# Main.net
KiCad netlist of a schematic drawn in Altium Designer
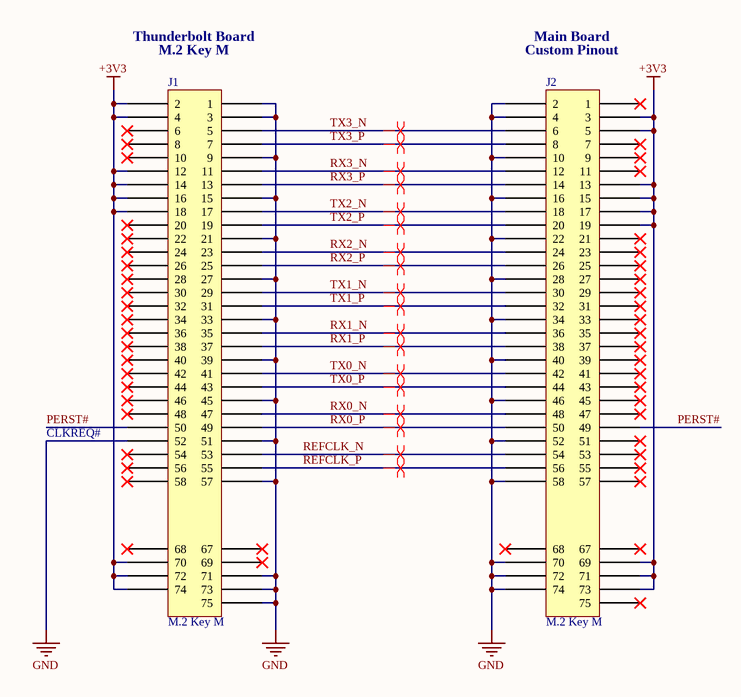
[diagram p0: Main.SchDoc]

(export (version "E")
  (design (tool "Eeschema 10.0.6"))
  (components
    (comp (ref "J1")
      (value "M.2 Key M")
      (footprint "PCB EDGE M.2 Key M")
      (libsource (lib "DSO") (part "M.2 Key M"))
    )
    (comp (ref "J2")
      (value "M.2 Key M")
      (footprint "PCB EDGE M.2 Key M")
      (libsource (lib "DSO") (part "M.2 Key M"))
    )
  )
  (nets
    (net (code "1") (name "+3V3") (class "Default")
      (node (ref "J1") (pin "12") (pinfunction "12_12") (pintype "passive"))
      (node (ref "J1") (pin "14") (pinfunction "14_14") (pintype "passive"))
      (node (ref "J1") (pin "16") (pinfunction "16_16") (pintype "passive"))
      (node (ref "J1") (pin "18") (pinfunction "18_18") (pintype "passive"))
      (node (ref "J1") (pin "2") (pinfunction "2_2") (pintype "passive"))
      (node (ref "J1") (pin "4") (pinfunction "4_4") (pintype "passive"))
      (node (ref "J1") (pin "70") (pinfunction "70_70") (pintype "passive"))
      (node (ref "J1") (pin "72") (pinfunction "72_72") (pintype "passive"))
      (node (ref "J1") (pin "74") (pinfunction "74_74") (pintype "passive"))
      (node (ref "J2") (pin "13") (pinfunction "13_13") (pintype "passive"))
      (node (ref "J2") (pin "15") (pinfunction "15_15") (pintype "passive"))
      (node (ref "J2") (pin "17") (pinfunction "17_17") (pintype "passive"))
      (node (ref "J2") (pin "19") (pinfunction "19_19") (pintype "passive"))
      (node (ref "J2") (pin "3") (pinfunction "3_3") (pintype "passive"))
      (node (ref "J2") (pin "5") (pinfunction "5_5") (pintype "passive"))
      (node (ref "J2") (pin "69") (pinfunction "69_69") (pintype "passive"))
      (node (ref "J2") (pin "71") (pinfunction "71_71") (pintype "passive"))
      (node (ref "J2") (pin "73") (pinfunction "73_73") (pintype "passive"))
    )
    (net (code "2") (name "/PERST#") (class "Default")
      (node (ref "J1") (pin "50") (pinfunction "50_50") (pintype "passive"))
      (node (ref "J2") (pin "49") (pinfunction "49_49") (pintype "passive"))
    )
    (net (code "3") (name "/REFCLK_N") (class "Default")
      (node (ref "J1") (pin "53") (pinfunction "53_53") (pintype "passive"))
      (node (ref "J2") (pin "54") (pinfunction "54_54") (pintype "passive"))
    )
    (net (code "4") (name "/REFCLK_P") (class "Default")
      (node (ref "J1") (pin "55") (pinfunction "55_55") (pintype "passive"))
      (node (ref "J2") (pin "56") (pinfunction "56_56") (pintype "passive"))
    )
    (net (code "5") (name "/RX0_N") (class "Default")
      (node (ref "J1") (pin "47") (pinfunction "47_47") (pintype "passive"))
      (node (ref "J2") (pin "48") (pinfunction "48_48") (pintype "passive"))
    )
    (net (code "6") (name "/RX0_P") (class "Default")
      (node (ref "J1") (pin "49") (pinfunction "49_49") (pintype "passive"))
      (node (ref "J2") (pin "50") (pinfunction "50_50") (pintype "passive"))
    )
    (net (code "7") (name "/RX1_N") (class "Default")
      (node (ref "J1") (pin "35") (pinfunction "35_35") (pintype "passive"))
      (node (ref "J2") (pin "36") (pinfunction "36_36") (pintype "passive"))
    )
    (net (code "8") (name "/RX1_P") (class "Default")
      (node (ref "J1") (pin "37") (pinfunction "37_37") (pintype "passive"))
      (node (ref "J2") (pin "38") (pinfunction "38_38") (pintype "passive"))
    )
    (net (code "9") (name "/RX2_N") (class "Default")
      (node (ref "J1") (pin "23") (pinfunction "23_23") (pintype "passive"))
      (node (ref "J2") (pin "24") (pinfunction "24_24") (pintype "passive"))
    )
    (net (code "10") (name "/RX2_P") (class "Default")
      (node (ref "J1") (pin "25") (pinfunction "25_25") (pintype "passive"))
      (node (ref "J2") (pin "26") (pinfunction "26_26") (pintype "passive"))
    )
    (net (code "11") (name "/RX3_N") (class "Default")
      (node (ref "J1") (pin "11") (pinfunction "11_11") (pintype "passive"))
      (node (ref "J2") (pin "12") (pinfunction "12_12") (pintype "passive"))
    )
    (net (code "12") (name "/RX3_P") (class "Default")
      (node (ref "J1") (pin "13") (pinfunction "13_13") (pintype "passive"))
      (node (ref "J2") (pin "14") (pinfunction "14_14") (pintype "passive"))
    )
    (net (code "13") (name "/TX0_N") (class "Default")
      (node (ref "J1") (pin "41") (pinfunction "41_41") (pintype "passive"))
      (node (ref "J2") (pin "42") (pinfunction "42_42") (pintype "passive"))
    )
    (net (code "14") (name "/TX0_P") (class "Default")
      (node (ref "J1") (pin "43") (pinfunction "43_43") (pintype "passive"))
      (node (ref "J2") (pin "44") (pinfunction "44_44") (pintype "passive"))
    )
    (net (code "15") (name "/TX1_N") (class "Default")
      (node (ref "J1") (pin "29") (pinfunction "29_29") (pintype "passive"))
      (node (ref "J2") (pin "30") (pinfunction "30_30") (pintype "passive"))
    )
    (net (code "16") (name "/TX1_P") (class "Default")
      (node (ref "J1") (pin "31") (pinfunction "31_31") (pintype "passive"))
      (node (ref "J2") (pin "32") (pinfunction "32_32") (pintype "passive"))
    )
    (net (code "17") (name "/TX2_N") (class "Default")
      (node (ref "J1") (pin "17") (pinfunction "17_17") (pintype "passive"))
      (node (ref "J2") (pin "18") (pinfunction "18_18") (pintype "passive"))
    )
    (net (code "18") (name "/TX2_P") (class "Default")
      (node (ref "J1") (pin "19") (pinfunction "19_19") (pintype "passive"))
      (node (ref "J2") (pin "20") (pinfunction "20_20") (pintype "passive"))
    )
    (net (code "19") (name "/TX3_N") (class "Default")
      (node (ref "J1") (pin "5") (pinfunction "5_5") (pintype "passive"))
      (node (ref "J2") (pin "6") (pinfunction "6_6") (pintype "passive"))
    )
    (net (code "20") (name "/TX3_P") (class "Default")
      (node (ref "J1") (pin "7") (pinfunction "7_7") (pintype "passive"))
      (node (ref "J2") (pin "8") (pinfunction "8_8") (pintype "passive"))
    )
    (net (code "21") (name "GND") (class "Default")
      (node (ref "J1") (pin "1") (pinfunction "1_1") (pintype "passive"))
      (node (ref "J1") (pin "15") (pinfunction "15_15") (pintype "passive"))
      (node (ref "J1") (pin "21") (pinfunction "21_21") (pintype "passive"))
      (node (ref "J1") (pin "27") (pinfunction "27_27") (pintype "passive"))
      (node (ref "J1") (pin "3") (pinfunction "3_3") (pintype "passive"))
      (node (ref "J1") (pin "33") (pinfunction "33_33") (pintype "passive"))
      (node (ref "J1") (pin "39") (pinfunction "39_39") (pintype "passive"))
      (node (ref "J1") (pin "45") (pinfunction "45_45") (pintype "passive"))
      (node (ref "J1") (pin "51") (pinfunction "51_51") (pintype "passive"))
      (node (ref "J1") (pin "52") (pinfunction "52_52") (pintype "passive"))
      (node (ref "J1") (pin "57") (pinfunction "57_57") (pintype "passive"))
      (node (ref "J1") (pin "71") (pinfunction "71_71") (pintype "passive"))
      (node (ref "J1") (pin "73") (pinfunction "73_73") (pintype "passive"))
      (node (ref "J1") (pin "75") (pinfunction "75_75") (pintype "passive"))
      (node (ref "J1") (pin "9") (pinfunction "9_9") (pintype "passive"))
      (node (ref "J2") (pin "10") (pinfunction "10_10") (pintype "passive"))
      (node (ref "J2") (pin "16") (pinfunction "16_16") (pintype "passive"))
      (node (ref "J2") (pin "2") (pinfunction "2_2") (pintype "passive"))
      (node (ref "J2") (pin "22") (pinfunction "22_22") (pintype "passive"))
      (node (ref "J2") (pin "28") (pinfunction "28_28") (pintype "passive"))
      (node (ref "J2") (pin "34") (pinfunction "34_34") (pintype "passive"))
      (node (ref "J2") (pin "4") (pinfunction "4_4") (pintype "passive"))
      (node (ref "J2") (pin "40") (pinfunction "40_40") (pintype "passive"))
      (node (ref "J2") (pin "46") (pinfunction "46_46") (pintype "passive"))
      (node (ref "J2") (pin "52") (pinfunction "52_52") (pintype "passive"))
      (node (ref "J2") (pin "58") (pinfunction "58_58") (pintype "passive"))
      (node (ref "J2") (pin "70") (pinfunction "70_70") (pintype "passive"))
      (node (ref "J2") (pin "72") (pinfunction "72_72") (pintype "passive"))
      (node (ref "J2") (pin "74") (pinfunction "74_74") (pintype "passive"))
    )
    (net (code "22") (name "unconnected-(J1-Pad6)") (class "Default")
      (node (ref "J1") (pin "6") (pinfunction "6_6") (pintype "passive+no_connect"))
    )
    (net (code "23") (name "unconnected-(J1-Pad8)") (class "Default")
      (node (ref "J1") (pin "8") (pinfunction "8_8") (pintype "passive+no_connect"))
    )
    (net (code "24") (name "unconnected-(J1-Pad10)") (class "Default")
      (node (ref "J1") (pin "10") (pinfunction "10_10") (pintype "passive+no_connect"))
    )
    (net (code "25") (name "unconnected-(J1-Pad20)") (class "Default")
      (node (ref "J1") (pin "20") (pinfunction "20_20") (pintype "passive+no_connect"))
    )
    (net (code "26") (name "unconnected-(J1-Pad22)") (class "Default")
      (node (ref "J1") (pin "22") (pinfunction "22_22") (pintype "passive+no_connect"))
    )
    (net (code "27") (name "unconnected-(J1-Pad24)") (class "Default")
      (node (ref "J1") (pin "24") (pinfunction "24_24") (pintype "passive+no_connect"))
    )
    (net (code "28") (name "unconnected-(J1-Pad26)") (class "Default")
      (node (ref "J1") (pin "26") (pinfunction "26_26") (pintype "passive+no_connect"))
    )
    (net (code "29") (name "unconnected-(J1-Pad28)") (class "Default")
      (node (ref "J1") (pin "28") (pinfunction "28_28") (pintype "passive+no_connect"))
    )
    (net (code "30") (name "unconnected-(J1-Pad30)") (class "Default")
      (node (ref "J1") (pin "30") (pinfunction "30_30") (pintype "passive+no_connect"))
    )
    (net (code "31") (name "unconnected-(J1-Pad32)") (class "Default")
      (node (ref "J1") (pin "32") (pinfunction "32_32") (pintype "passive+no_connect"))
    )
    (net (code "32") (name "unconnected-(J1-Pad34)") (class "Default")
      (node (ref "J1") (pin "34") (pinfunction "34_34") (pintype "passive+no_connect"))
    )
    (net (code "33") (name "unconnected-(J1-Pad36)") (class "Default")
      (node (ref "J1") (pin "36") (pinfunction "36_36") (pintype "passive+no_connect"))
    )
    (net (code "34") (name "unconnected-(J1-Pad38)") (class "Default")
      (node (ref "J1") (pin "38") (pinfunction "38_38") (pintype "passive+no_connect"))
    )
    (net (code "35") (name "unconnected-(J1-Pad40)") (class "Default")
      (node (ref "J1") (pin "40") (pinfunction "40_40") (pintype "passive+no_connect"))
    )
    (net (code "36") (name "unconnected-(J1-Pad42)") (class "Default")
      (node (ref "J1") (pin "42") (pinfunction "42_42") (pintype "passive+no_connect"))
    )
    (net (code "37") (name "unconnected-(J1-Pad44)") (class "Default")
      (node (ref "J1") (pin "44") (pinfunction "44_44") (pintype "passive+no_connect"))
    )
    (net (code "38") (name "unconnected-(J1-Pad46)") (class "Default")
      (node (ref "J1") (pin "46") (pinfunction "46_46") (pintype "passive+no_connect"))
    )
    (net (code "39") (name "unconnected-(J1-Pad48)") (class "Default")
      (node (ref "J1") (pin "48") (pinfunction "48_48") (pintype "passive+no_connect"))
    )
    (net (code "40") (name "unconnected-(J1-Pad54)") (class "Default")
      (node (ref "J1") (pin "54") (pinfunction "54_54") (pintype "passive+no_connect"))
    )
    (net (code "41") (name "unconnected-(J1-Pad56)") (class "Default")
      (node (ref "J1") (pin "56") (pinfunction "56_56") (pintype "passive+no_connect"))
    )
    (net (code "42") (name "unconnected-(J1-Pad58)") (class "Default")
      (node (ref "J1") (pin "58") (pinfunction "58_58") (pintype "passive+no_connect"))
    )
    (net (code "43") (name "unconnected-(J1-Pad67)") (class "Default")
      (node (ref "J1") (pin "67") (pinfunction "67_67") (pintype "passive+no_connect"))
    )
    (net (code "44") (name "unconnected-(J1-Pad68)") (class "Default")
      (node (ref "J1") (pin "68") (pinfunction "68_68") (pintype "passive+no_connect"))
    )
    (net (code "45") (name "unconnected-(J1-Pad69)") (class "Default")
      (node (ref "J1") (pin "69") (pinfunction "69_69") (pintype "passive+no_connect"))
    )
    (net (code "46") (name "unconnected-(J2-Pad1)") (class "Default")
      (node (ref "J2") (pin "1") (pinfunction "1_1") (pintype "passive+no_connect"))
    )
    (net (code "47") (name "unconnected-(J2-Pad7)") (class "Default")
      (node (ref "J2") (pin "7") (pinfunction "7_7") (pintype "passive+no_connect"))
    )
    (net (code "48") (name "unconnected-(J2-Pad9)") (class "Default")
      (node (ref "J2") (pin "9") (pinfunction "9_9") (pintype "passive+no_connect"))
    )
    (net (code "49") (name "unconnected-(J2-Pad11)") (class "Default")
      (node (ref "J2") (pin "11") (pinfunction "11_11") (pintype "passive+no_connect"))
    )
    (net (code "50") (name "unconnected-(J2-Pad21)") (class "Default")
      (node (ref "J2") (pin "21") (pinfunction "21_21") (pintype "passive+no_connect"))
    )
    (net (code "51") (name "unconnected-(J2-Pad23)") (class "Default")
      (node (ref "J2") (pin "23") (pinfunction "23_23") (pintype "passive+no_connect"))
    )
    (net (code "52") (name "unconnected-(J2-Pad25)") (class "Default")
      (node (ref "J2") (pin "25") (pinfunction "25_25") (pintype "passive+no_connect"))
    )
    (net (code "53") (name "unconnected-(J2-Pad27)") (class "Default")
      (node (ref "J2") (pin "27") (pinfunction "27_27") (pintype "passive+no_connect"))
    )
    (net (code "54") (name "unconnected-(J2-Pad29)") (class "Default")
      (node (ref "J2") (pin "29") (pinfunction "29_29") (pintype "passive+no_connect"))
    )
    (net (code "55") (name "unconnected-(J2-Pad31)") (class "Default")
      (node (ref "J2") (pin "31") (pinfunction "31_31") (pintype "passive+no_connect"))
    )
    (net (code "56") (name "unconnected-(J2-Pad33)") (class "Default")
      (node (ref "J2") (pin "33") (pinfunction "33_33") (pintype "passive+no_connect"))
    )
    (net (code "57") (name "unconnected-(J2-Pad35)") (class "Default")
      (node (ref "J2") (pin "35") (pinfunction "35_35") (pintype "passive+no_connect"))
    )
    (net (code "58") (name "unconnected-(J2-Pad37)") (class "Default")
      (node (ref "J2") (pin "37") (pinfunction "37_37") (pintype "passive+no_connect"))
    )
    (net (code "59") (name "unconnected-(J2-Pad39)") (class "Default")
      (node (ref "J2") (pin "39") (pinfunction "39_39") (pintype "passive+no_connect"))
    )
    (net (code "60") (name "unconnected-(J2-Pad41)") (class "Default")
      (node (ref "J2") (pin "41") (pinfunction "41_41") (pintype "passive+no_connect"))
    )
    (net (code "61") (name "unconnected-(J2-Pad43)") (class "Default")
      (node (ref "J2") (pin "43") (pinfunction "43_43") (pintype "passive+no_connect"))
    )
    (net (code "62") (name "unconnected-(J2-Pad45)") (class "Default")
      (node (ref "J2") (pin "45") (pinfunction "45_45") (pintype "passive+no_connect"))
    )
    (net (code "63") (name "unconnected-(J2-Pad47)") (class "Default")
      (node (ref "J2") (pin "47") (pinfunction "47_47") (pintype "passive+no_connect"))
    )
    (net (code "64") (name "unconnected-(J2-Pad51)") (class "Default")
      (node (ref "J2") (pin "51") (pinfunction "51_51") (pintype "passive+no_connect"))
    )
    (net (code "65") (name "unconnected-(J2-Pad53)") (class "Default")
      (node (ref "J2") (pin "53") (pinfunction "53_53") (pintype "passive+no_connect"))
    )
    (net (code "66") (name "unconnected-(J2-Pad55)") (class "Default")
      (node (ref "J2") (pin "55") (pinfunction "55_55") (pintype "passive+no_connect"))
    )
    (net (code "67") (name "unconnected-(J2-Pad57)") (class "Default")
      (node (ref "J2") (pin "57") (pinfunction "57_57") (pintype "passive+no_connect"))
    )
    (net (code "68") (name "unconnected-(J2-Pad67)") (class "Default")
      (node (ref "J2") (pin "67") (pinfunction "67_67") (pintype "passive+no_connect"))
    )
    (net (code "69") (name "unconnected-(J2-Pad68)") (class "Default")
      (node (ref "J2") (pin "68") (pinfunction "68_68") (pintype "passive+no_connect"))
    )
    (net (code "70") (name "unconnected-(J2-Pad75)") (class "Default")
      (node (ref "J2") (pin "75") (pinfunction "75_75") (pintype "passive+no_connect"))
    )
  )
)
